# Day10F206.net
KiCad netlist of a schematic drawn in Altium Designer
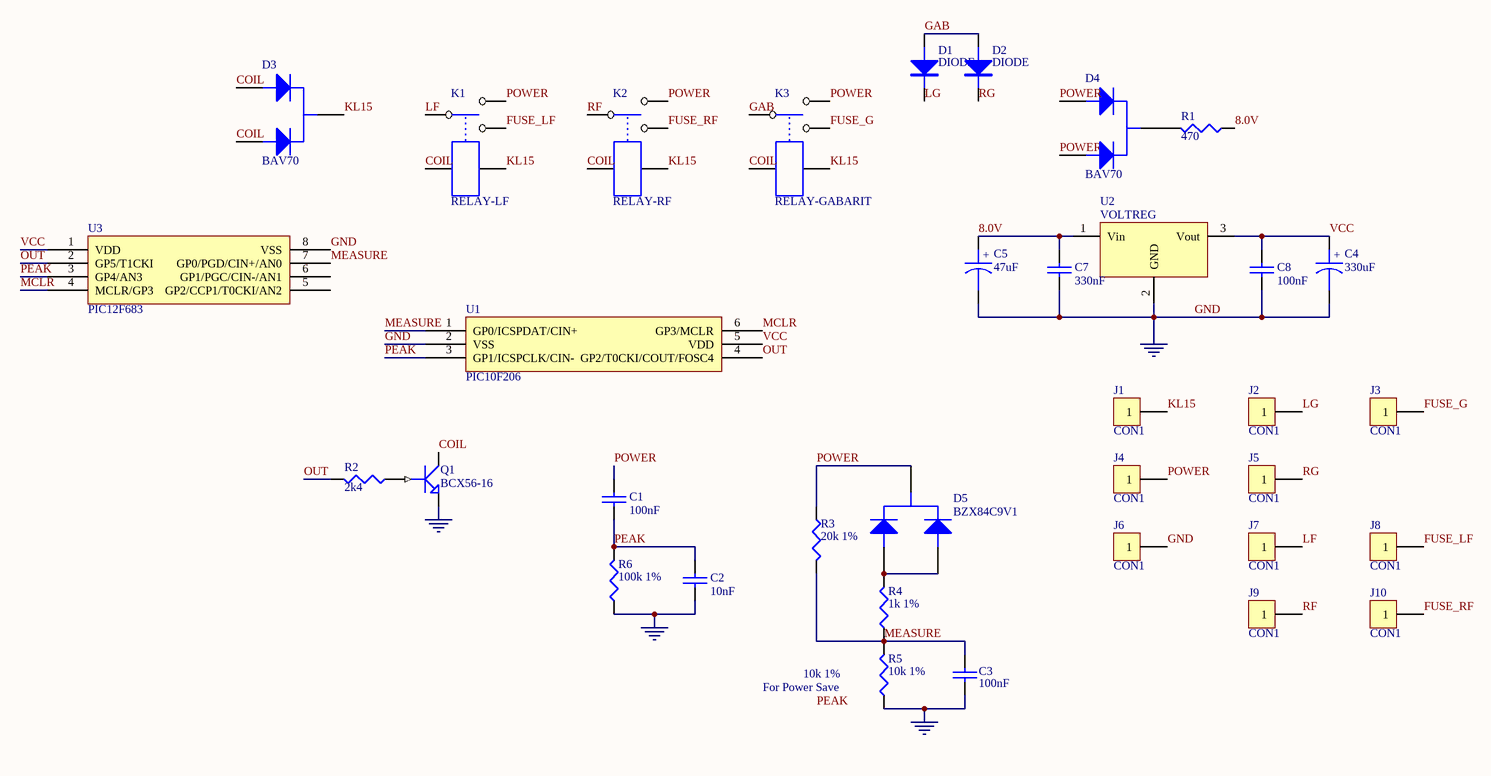
[diagram p0: Day10F206.SchDoc]

(export (version "E")
  (design (tool "Eeschema 10.0.6"))
  (components
    (comp (ref "C1")
      (value "100nF")
      (footprint "0805")
      (description "Capacitor")
      (libsource (lib "*") (part "CAP"))
    )
    (comp (ref "C2")
      (value "10nF")
      (footprint "0603")
      (description "Capacitor")
      (libsource (lib "*") (part "CAP"))
    )
    (comp (ref "C3")
      (value "100nF")
      (footprint "0603")
      (description "Capacitor")
      (libsource (lib "*") (part "CAP"))
    )
    (comp (ref "C4")
      (value "330uF")
      (footprint "RA 6.3mm")
      (description "Capacitor")
      (libsource (lib "*") (part "CAPACITOR POL"))
    )
    (comp (ref "C5")
      (value "47uF")
      (footprint "RA 6.3mm")
      (description "Capacitor")
      (libsource (lib "*") (part "CAPACITOR POL"))
    )
    (comp (ref "C7")
      (value "330nF")
      (footprint "0805")
      (description "Capacitor")
      (libsource (lib "*") (part "CAP"))
    )
    (comp (ref "C8")
      (value "100nF")
      (footprint "0805")
      (description "Capacitor")
      (libsource (lib "*") (part "CAP"))
    )
    (comp (ref "D1")
      (value "DIODE")
      (footprint "DIODE0.7 Radial")
      (description "Diode")
      (libsource (lib "Miscellaneous Devices") (part "DIODE"))
    )
    (comp (ref "D2")
      (value "DIODE")
      (footprint "DIODE0.7 Radial")
      (description "Diode")
      (libsource (lib "Miscellaneous Devices") (part "DIODE"))
    )
    (comp (ref "D3")
      (value "BAV70")
      (footprint "SOT-23")
      (libsource (lib "Devices") (part "DUAL DIODE BAV70"))
    )
    (comp (ref "D4")
      (value "BAV70")
      (footprint "SOT-23")
      (libsource (lib "Devices") (part "DUAL DIODE BAV70"))
    )
    (comp (ref "D5")
      (value "BZX84C9V1")
      (footprint "SOT-23")
      (libsource (lib "Devices") (part "DUAL DIODE BAV70"))
    )
    (comp (ref "J1")
      (value "CON1")
      (footprint "SIP1 - WIRE")
      (description "Connector")
      (libsource (lib "Miscellaneous Devices") (part "CON1"))
    )
    (comp (ref "J2")
      (value "CON1")
      (footprint "SIP1 - WIRE")
      (description "Connector")
      (libsource (lib "Miscellaneous Devices") (part "CON1"))
    )
    (comp (ref "J3")
      (value "CON1")
      (footprint "SIP1 - WIRE")
      (description "Connector")
      (libsource (lib "Miscellaneous Devices") (part "CON1"))
    )
    (comp (ref "J4")
      (value "CON1")
      (footprint "SIP1 - WIRE")
      (description "Connector")
      (libsource (lib "Miscellaneous Devices") (part "CON1"))
    )
    (comp (ref "J5")
      (value "CON1")
      (footprint "SIP1 - WIRE")
      (description "Connector")
      (libsource (lib "Miscellaneous Devices") (part "CON1"))
    )
    (comp (ref "J6")
      (value "CON1")
      (footprint "SIP1 - WIRE")
      (description "Connector")
      (libsource (lib "Miscellaneous Devices") (part "CON1"))
    )
    (comp (ref "J7")
      (value "CON1")
      (footprint "SIP1 - WIRE")
      (description "Connector")
      (libsource (lib "Miscellaneous Devices") (part "CON1"))
    )
    (comp (ref "J8")
      (value "CON1")
      (footprint "SIP1 - WIRE")
      (description "Connector")
      (libsource (lib "Miscellaneous Devices") (part "CON1"))
    )
    (comp (ref "J9")
      (value "CON1")
      (footprint "SIP1 - WIRE")
      (description "Connector")
      (libsource (lib "Miscellaneous Devices") (part "CON1"))
    )
    (comp (ref "J10")
      (value "CON1")
      (footprint "SIP1 - WIRE")
      (description "Connector")
      (libsource (lib "Miscellaneous Devices") (part "CON1"))
    )
    (comp (ref "K1")
      (value "RELAY-LF")
      (footprint "RELAY5PIN")
      (libsource (lib "Miscellaneous Devices") (part "RELAY-SPDT"))
    )
    (comp (ref "K2")
      (value "RELAY-RF")
      (footprint "RELAY5PIN")
      (libsource (lib "Miscellaneous Devices") (part "RELAY-SPDT"))
    )
    (comp (ref "K3")
      (value "RELAY-GABARIT")
      (footprint "RELAY5PIN")
      (libsource (lib "Miscellaneous Devices") (part "RELAY-SPDT"))
    )
    (comp (ref "Q1")
      (value "BCX56-16")
      (footprint "SOT-89")
      (description "NPN Transistor")
      (libsource (lib "Miscellaneous Devices") (part "NPN1"))
    )
    (comp (ref "R1") (value "470") (footprint "0805") (libsource (lib "Miscellaneous Devices") (part "RES1")))
    (comp (ref "R2") (value "2k4") (footprint "0603") (libsource (lib "Miscellaneous Devices") (part "RES1")))
    (comp (ref "R3")
      (value "20k 1%")
      (footprint "0603")
      (libsource (lib "Miscellaneous Devices") (part "RES1"))
    )
    (comp (ref "R4")
      (value "1k 1%")
      (footprint "0603")
      (libsource (lib "Miscellaneous Devices") (part "RES1"))
    )
    (comp (ref "R5")
      (value "10k 1%")
      (footprint "0603")
      (libsource (lib "Miscellaneous Devices") (part "RES1"))
    )
    (comp (ref "R6")
      (value "100k 1%")
      (footprint "0603")
      (libsource (lib "Miscellaneous Devices") (part "RES1"))
    )
    (comp (ref "U1")
      (value "PIC10F206")
      (footprint "SOT-23 - 6 WIDE")
      (libsource (lib "MCU") (part "PIC10F206"))
    )
    (comp (ref "U2") (value "VOLTREG") (footprint "TO-92B") (libsource (lib "*") (part "VOLTREG")))
    (comp (ref "U3") (value "PIC12F683") (footprint "SO-8") (libsource (lib "MCU") (part "PIC12F683")))
  )
  (nets
    (net (code "1") (name "/8.0V") (class "Default")
      (node (ref "C5") (pin "1") (pinfunction "1_1") (pintype "passive"))
      (node (ref "C7") (pin "1") (pinfunction "1_1") (pintype "passive"))
      (node (ref "R1") (pin "1") (pinfunction "1_1") (pintype "passive"))
      (node (ref "U2") (pin "1") (pinfunction "Vin_1") (pintype "passive"))
    )
    (net (code "2") (name "/COIL") (class "Default")
      (node (ref "D3") (pin "1") (pinfunction "A1_1") (pintype "passive"))
      (node (ref "D3") (pin "3") (pinfunction "A2_3") (pintype "passive"))
      (node (ref "K1") (pin "4") (pinfunction "4_4") (pintype "passive"))
      (node (ref "K2") (pin "4") (pinfunction "4_4") (pintype "passive"))
      (node (ref "K3") (pin "4") (pinfunction "4_4") (pintype "passive"))
      (node (ref "Q1") (pin "2") (pinfunction "C_2") (pintype "passive"))
    )
    (net (code "3") (name "/FUSE_G") (class "Default")
      (node (ref "J3") (pin "1") (pinfunction "1_1") (pintype "passive"))
      (node (ref "K3") (pin "3") (pinfunction "3_3") (pintype "passive"))
    )
    (net (code "4") (name "/FUSE_LF") (class "Default")
      (node (ref "J8") (pin "1") (pinfunction "1_1") (pintype "passive"))
      (node (ref "K1") (pin "3") (pinfunction "3_3") (pintype "passive"))
    )
    (net (code "5") (name "/FUSE_RF") (class "Default")
      (node (ref "J10") (pin "1") (pinfunction "1_1") (pintype "passive"))
      (node (ref "K2") (pin "3") (pinfunction "3_3") (pintype "passive"))
    )
    (net (code "6") (name "/GAB") (class "Default")
      (node (ref "D1") (pin "A") (pinfunction "A_A") (pintype "passive"))
      (node (ref "D2") (pin "A") (pinfunction "A_A") (pintype "passive"))
      (node (ref "K3") (pin "1") (pinfunction "1_1") (pintype "passive"))
    )
    (net (code "7") (name "/KL15") (class "Default")
      (node (ref "D3") (pin "2") (pinfunction "K_2") (pintype "passive"))
      (node (ref "J1") (pin "1") (pinfunction "1_1") (pintype "passive"))
      (node (ref "K1") (pin "5") (pinfunction "5_5") (pintype "passive"))
      (node (ref "K2") (pin "5") (pinfunction "5_5") (pintype "passive"))
      (node (ref "K3") (pin "5") (pinfunction "5_5") (pintype "passive"))
    )
    (net (code "8") (name "/LF") (class "Default")
      (node (ref "J7") (pin "1") (pinfunction "1_1") (pintype "passive"))
      (node (ref "K1") (pin "1") (pinfunction "1_1") (pintype "passive"))
    )
    (net (code "9") (name "/LG") (class "Default")
      (node (ref "D1") (pin "K") (pinfunction "K_K") (pintype "passive"))
      (node (ref "J2") (pin "1") (pinfunction "1_1") (pintype "passive"))
    )
    (net (code "10") (name "/MCLR") (class "Default")
      (node (ref "U1") (pin "6") (pinfunction "GP3/MCLR_6") (pintype "passive"))
      (node (ref "U3") (pin "4") (pinfunction "MCLR/GP3_4") (pintype "passive"))
    )
    (net (code "11") (name "/MEASURE") (class "Default")
      (node (ref "C3") (pin "2") (pinfunction "2_2") (pintype "passive"))
      (node (ref "R3") (pin "2") (pinfunction "2_2") (pintype "passive"))
      (node (ref "R4") (pin "1") (pinfunction "1_1") (pintype "passive"))
      (node (ref "R5") (pin "2") (pinfunction "2_2") (pintype "passive"))
      (node (ref "U1") (pin "1") (pinfunction "GP0/ICSPDAT/CIN+_1") (pintype "passive"))
      (node (ref "U3") (pin "7") (pinfunction "GP0/PGD/CIN+/AN0_7") (pintype "passive"))
    )
    (net (code "12") (name "/OUT") (class "Default")
      (node (ref "R2") (pin "2") (pinfunction "2_2") (pintype "passive"))
      (node (ref "U1") (pin "4") (pinfunction "GP2/T0CKI/COUT/FOSC4_4") (pintype "passive"))
      (node (ref "U3") (pin "2") (pinfunction "GP5/T1CKI_2") (pintype "passive"))
    )
    (net (code "13") (name "/PEAK") (class "Default")
      (node (ref "C1") (pin "2") (pinfunction "2_2") (pintype "passive"))
      (node (ref "C2") (pin "1") (pinfunction "1_1") (pintype "passive"))
      (node (ref "R6") (pin "2") (pinfunction "2_2") (pintype "passive"))
      (node (ref "U1") (pin "3") (pinfunction "GP1/ICSPCLK/CIN-_3") (pintype "passive"))
      (node (ref "U3") (pin "3") (pinfunction "GP4/AN3_3") (pintype "passive"))
    )
    (net (code "14") (name "/POWER") (class "Default")
      (node (ref "C1") (pin "1") (pinfunction "1_1") (pintype "passive"))
      (node (ref "D4") (pin "1") (pinfunction "A1_1") (pintype "passive"))
      (node (ref "D4") (pin "3") (pinfunction "A2_3") (pintype "passive"))
      (node (ref "D5") (pin "2") (pinfunction "K_2") (pintype "passive"))
      (node (ref "J4") (pin "1") (pinfunction "1_1") (pintype "passive"))
      (node (ref "K1") (pin "2") (pinfunction "2_2") (pintype "passive"))
      (node (ref "K2") (pin "2") (pinfunction "2_2") (pintype "passive"))
      (node (ref "K3") (pin "2") (pinfunction "2_2") (pintype "passive"))
      (node (ref "R3") (pin "1") (pinfunction "1_1") (pintype "passive"))
    )
    (net (code "15") (name "/RF") (class "Default")
      (node (ref "J9") (pin "1") (pinfunction "1_1") (pintype "passive"))
      (node (ref "K2") (pin "1") (pinfunction "1_1") (pintype "passive"))
    )
    (net (code "16") (name "/RG") (class "Default")
      (node (ref "D2") (pin "K") (pinfunction "K_K") (pintype "passive"))
      (node (ref "J5") (pin "1") (pinfunction "1_1") (pintype "passive"))
    )
    (net (code "17") (name "/VCC") (class "Default")
      (node (ref "C4") (pin "1") (pinfunction "1_1") (pintype "passive"))
      (node (ref "C8") (pin "1") (pinfunction "1_1") (pintype "passive"))
      (node (ref "U1") (pin "5") (pinfunction "VDD_5") (pintype "passive"))
      (node (ref "U2") (pin "3") (pinfunction "Vout_3") (pintype "passive"))
      (node (ref "U3") (pin "1") (pinfunction "VDD_1") (pintype "passive"))
    )
    (net (code "18") (name "GND") (class "Default")
      (node (ref "C2") (pin "2") (pinfunction "2_2") (pintype "passive"))
      (node (ref "C3") (pin "1") (pinfunction "1_1") (pintype "passive"))
      (node (ref "C4") (pin "2") (pinfunction "2_2") (pintype "passive"))
      (node (ref "C5") (pin "2") (pinfunction "2_2") (pintype "passive"))
      (node (ref "C7") (pin "2") (pinfunction "2_2") (pintype "passive"))
      (node (ref "C8") (pin "2") (pinfunction "2_2") (pintype "passive"))
      (node (ref "J6") (pin "1") (pinfunction "1_1") (pintype "passive"))
      (node (ref "Q1") (pin "3") (pinfunction "E_3") (pintype "passive"))
      (node (ref "R5") (pin "1") (pinfunction "1_1") (pintype "passive"))
      (node (ref "R6") (pin "1") (pinfunction "1_1") (pintype "passive"))
      (node (ref "U1") (pin "2") (pinfunction "VSS_2") (pintype "passive"))
      (node (ref "U2") (pin "2") (pinfunction "GND_2") (pintype "passive"))
      (node (ref "U3") (pin "8") (pinfunction "VSS_8") (pintype "passive"))
    )
    (net (code "19") (name "Net-(D4-K)") (class "Default")
      (node (ref "D4") (pin "2") (pinfunction "K_2") (pintype "passive"))
      (node (ref "R1") (pin "2") (pinfunction "2_2") (pintype "passive"))
    )
    (net (code "20") (name "Net-(D5-A1)") (class "Default")
      (node (ref "D5") (pin "1") (pinfunction "A1_1") (pintype "passive"))
      (node (ref "D5") (pin "3") (pinfunction "A2_3") (pintype "passive"))
      (node (ref "R4") (pin "2") (pinfunction "2_2") (pintype "passive"))
    )
    (net (code "21") (name "Net-(Q1-B)") (class "Default")
      (node (ref "Q1") (pin "1") (pinfunction "B_1") (pintype "input"))
      (node (ref "R2") (pin "1") (pinfunction "1_1") (pintype "passive"))
    )
    (net (code "22") (name "unconnected-(U3-GP1{slash}PGC{slash}CIN-{slash}AN1-Pad6)") (class "Default")
      (node (ref "U3") (pin "6") (pinfunction "GP1/PGC/CIN-/AN1_6") (pintype "passive"))
    )
    (net (code "23") (name "unconnected-(U3-GP2{slash}CCP1{slash}T0CKI{slash}AN2-Pad5)") (class "Default")
      (node (ref "U3") (pin "5") (pinfunction "GP2/CCP1/T0CKI/AN2_5") (pintype "passive"))
    )
  )
)
